# Dogfish3D_-_Thermistor_Channel.net
KiCad netlist of a schematic drawn in Altium Designer
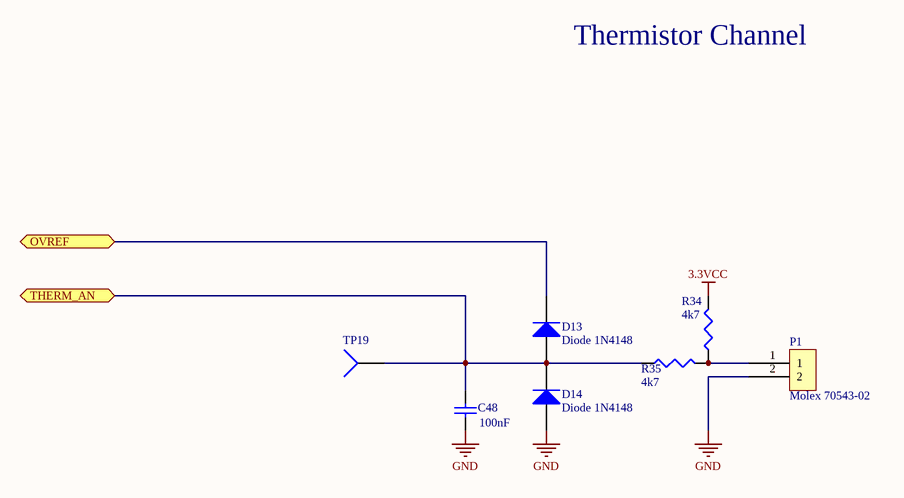
[diagram p0: Dogfish3D - Thermistor Channel.SchDoc]

(export (version "E")
  (design (tool "Eeschema 10.0.6"))
  (components
    (comp (ref "C48")
      (value "100nF")
      (footprint "1608[0603]")
      (description "Capacitor (Semiconductor SIM Model)")
      (fields (field (name "Comment") "Cap Semi") (field (name "PUBLISHER") "Altium Limited"))
      (libsource (lib "Miscellaneous Devices") (part "Cap Semi"))
    )
    (comp (ref "D13")
      (value "Diode 1N4148")
      (footprint "1N4148WT")
      (description "High Conductance Fast Diode")
      (fields (field (name "PUBLISHER") "Altium Limited"))
      (libsource (lib "Miscellaneous Devices") (part "Diode 1N4148"))
    )
    (comp (ref "D14")
      (value "Diode 1N4148")
      (footprint "1N4148WT")
      (description "High Conductance Fast Diode")
      (fields (field (name "PUBLISHER") "Altium Limited"))
      (libsource (lib "Miscellaneous Devices") (part "Diode 1N4148"))
    )
    (comp (ref "P1")
      (value "Molex 70543-02")
      (footprint "70543-02")
      (libsource (lib "ZMBo Schematic Library") (part "Molex 70543-02"))
    )
    (comp (ref "R34")
      (value "4k7")
      (footprint "J1-0603")
      (description "Resistor")
      (fields (field (name "Comment") "Res3") (field (name "PUBLISHER") "Altium Limited"))
      (libsource (lib "Miscellaneous Devices") (part "Res3"))
    )
    (comp (ref "R35")
      (value "4k7")
      (footprint "J1-0603")
      (description "Resistor")
      (fields (field (name "Comment") "Res3") (field (name "PUBLISHER") "Altium Limited"))
      (libsource (lib "Miscellaneous Devices") (part "Res3"))
    )
    (comp (ref "TP19")
      (value "TP4")
      (footprint "TP-2")
      (description "Socket")
      (fields (field (name "PUBLISHER") "Altium Limited"))
      (libsource (lib "ZMBo Schematic Library") (part "Socket"))
    )
  )
  (nets
    (net (code "1") (name "/OVREF") (class "Default")
      (node (ref "D13") (pin "2") (pinfunction "K_2") (pintype "passive"))
    )
    (net (code "2") (name "/THERM_AN") (class "Default")
      (node (ref "C48") (pin "2") (pinfunction "2_2") (pintype "passive"))
      (node (ref "D13") (pin "1") (pinfunction "A_1") (pintype "passive"))
      (node (ref "D14") (pin "2") (pinfunction "K_2") (pintype "passive"))
      (node (ref "R35") (pin "1") (pinfunction "1_1") (pintype "passive"))
      (node (ref "TP19") (pin "1") (pinfunction "1_1") (pintype "passive"))
    )
    (net (code "3") (name "3.3VCC") (class "Default")
      (node (ref "R34") (pin "2") (pinfunction "2_2") (pintype "passive"))
    )
    (net (code "4") (name "GND") (class "Default")
      (node (ref "C48") (pin "1") (pinfunction "1_1") (pintype "passive"))
      (node (ref "D14") (pin "1") (pinfunction "A_1") (pintype "passive"))
      (node (ref "P1") (pin "2") (pinfunction "2_2") (pintype "passive"))
    )
    (net (code "5") (name "Net-(P1-Pad1)") (class "Default")
      (node (ref "P1") (pin "1") (pinfunction "1_1") (pintype "passive"))
      (node (ref "R34") (pin "1") (pinfunction "1_1") (pintype "passive"))
      (node (ref "R35") (pin "2") (pinfunction "2_2") (pintype "passive"))
    )
  )
)
